# Light_Circuit.net
KiCad netlist of a schematic drawn in Altium Designer
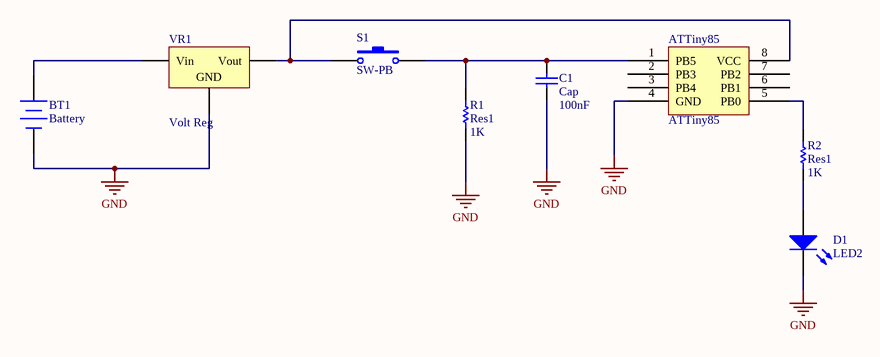
[diagram p0: Light_Circuit.SchDoc]

(export (version "E")
  (design (tool "Eeschema 10.0.6"))
  (components
    (comp (ref "ATTiny85")
      (value "ATTiny85")
      (footprint "8S2")
      (libsource (lib "lightSCHLib") (part "ATTiny85_1"))
    )
    (comp (ref "BT1")
      (value "Battery")
      (footprint "BAT-2")
      (description "Multicell Battery")
      (fields (field (name "PUBLISHER") "Altium Limited"))
      (libsource (lib "Miscellaneous Devices") (part "Battery"))
    )
    (comp (ref "C1")
      (value "Cap")
      (footprint "RAD-0.3")
      (description "Capacitor")
      (fields (field (name "ALTIUM_VALUE") "100nF") (field (name "PUBLISHER") "Altium Limited"))
      (libsource (lib "Miscellaneous Devices") (part "Cap"))
    )
    (comp (ref "D1")
      (value "LED2")
      (footprint "3.2X1.6X1.1")
      (description "Typical RED, GREEN, YELLOW, AMBER GaAs LED")
      (fields (field (name "PUBLISHER") "Altium Limited"))
      (libsource (lib "Miscellaneous Devices") (part "LED2"))
    )
    (comp (ref "R1")
      (value "Res1")
      (footprint "AXIAL-0.3")
      (description "Resistor")
      (fields (field (name "ALTIUM_VALUE") "1K") (field (name "PUBLISHER") "Altium Limited"))
      (libsource (lib "Miscellaneous Devices") (part "Res1"))
    )
    (comp (ref "R2")
      (value "Res1")
      (footprint "AXIAL-0.3")
      (description "Resistor")
      (fields (field (name "ALTIUM_VALUE") "1K") (field (name "PUBLISHER") "Altium Limited"))
      (libsource (lib "Miscellaneous Devices") (part "Res1"))
    )
    (comp (ref "S1")
      (value "SW-PB")
      (footprint "SPST-2")
      (description "Switch")
      (fields (field (name "PUBLISHER") "Altium Limited"))
      (libsource (lib "Miscellaneous Devices") (part "SW-PB"))
    )
    (comp (ref "VR1")
      (value "Volt Reg")
      (footprint "D2PAK_N")
      (description "Voltage Regulator")
      (fields (field (name "PUBLISHER") "Altium Limited"))
      (libsource (lib "Miscellaneous Devices") (part "Volt Reg"))
    )
  )
  (nets
    (net (code "1") (name "GND") (class "Default")
      (node (ref "ATTiny85") (pin "4") (pinfunction "GND_4") (pintype "passive"))
      (node (ref "BT1") (pin "2") (pinfunction "-_2") (pintype "passive"))
      (node (ref "C1") (pin "2") (pinfunction "2_2") (pintype "passive"))
      (node (ref "D1") (pin "2") (pinfunction "K_2") (pintype "passive"))
      (node (ref "R1") (pin "1") (pinfunction "1_1") (pintype "passive"))
      (node (ref "VR1") (pin "2") (pinfunction "GND_2") (pintype "passive"))
    )
    (net (code "2") (name "Net-(ATTiny85-PB0)") (class "Default")
      (node (ref "ATTiny85") (pin "5") (pinfunction "PB0_5") (pintype "passive"))
      (node (ref "R2") (pin "2") (pinfunction "2_2") (pintype "passive"))
    )
    (net (code "3") (name "Net-(ATTiny85-PB5)") (class "Default")
      (node (ref "ATTiny85") (pin "1") (pinfunction "PB5_1") (pintype "passive"))
      (node (ref "C1") (pin "1") (pinfunction "1_1") (pintype "passive"))
      (node (ref "R1") (pin "2") (pinfunction "2_2") (pintype "passive"))
      (node (ref "S1") (pin "2") (pinfunction "2_2") (pintype "passive"))
    )
    (net (code "4") (name "Net-(ATTiny85-VCC)") (class "Default")
      (node (ref "ATTiny85") (pin "8") (pinfunction "VCC_8") (pintype "passive"))
      (node (ref "S1") (pin "1") (pinfunction "1_1") (pintype "passive"))
      (node (ref "VR1") (pin "3") (pinfunction "Vout_3") (pintype "passive"))
    )
    (net (code "5") (name "Net-(BT1-+)") (class "Default")
      (node (ref "BT1") (pin "1") (pinfunction "+_1") (pintype "passive"))
      (node (ref "VR1") (pin "1") (pinfunction "Vin_1") (pintype "passive"))
    )
    (net (code "6") (name "Net-(D1-A)") (class "Default")
      (node (ref "D1") (pin "1") (pinfunction "A_1") (pintype "passive"))
      (node (ref "R2") (pin "1") (pinfunction "1_1") (pintype "passive"))
    )
    (net (code "7") (name "unconnected-(ATTiny85-PB1-Pad6)") (class "Default")
      (node (ref "ATTiny85") (pin "6") (pinfunction "PB1_6") (pintype "passive"))
    )
    (net (code "8") (name "unconnected-(ATTiny85-PB2-Pad7)") (class "Default")
      (node (ref "ATTiny85") (pin "7") (pinfunction "PB2_7") (pintype "passive"))
    )
    (net (code "9") (name "unconnected-(ATTiny85-PB3-Pad2)") (class "Default")
      (node (ref "ATTiny85") (pin "2") (pinfunction "PB3_2") (pintype "passive"))
    )
    (net (code "10") (name "unconnected-(ATTiny85-PB4-Pad3)") (class "Default")
      (node (ref "ATTiny85") (pin "3") (pinfunction "PB4_3") (pintype "passive"))
    )
  )
)
